# pcb-breakout-bmd300.net
KiCad netlist of a schematic drawn in EAGLE
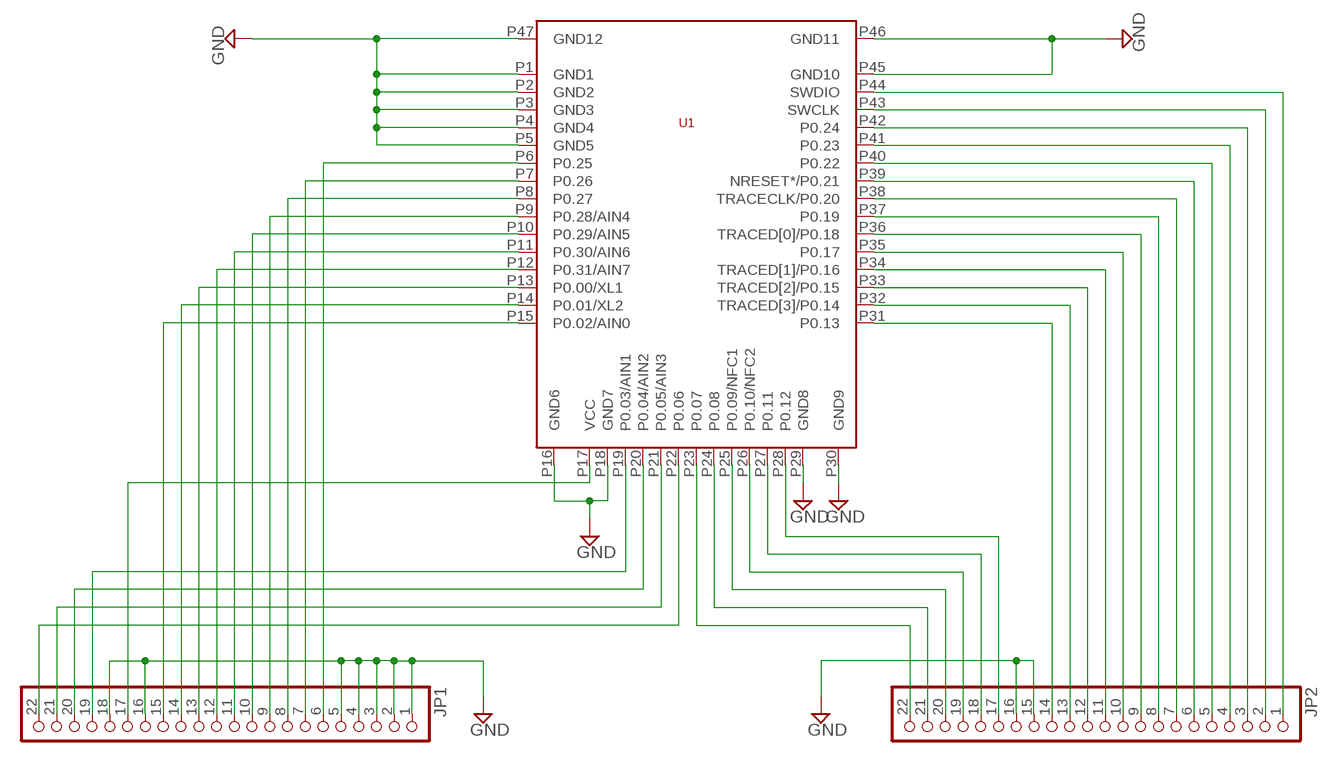
[diagram p0: schematic, sheet 1]

(export (version "E")
  (design (tool "Eeschema 10.0.6"))
  (components
    (comp (ref "JP1")
      (value "PINHD-1X22")
      (footprint "eagle-import:1X22")
      (libsource (lib "eagle-import") (part "PINHD-1X22"))
    )
    (comp (ref "JP2")
      (value "PINHD-1X22")
      (footprint "eagle-import:1X22")
      (libsource (lib "eagle-import") (part "PINHD-1X22"))
    )
    (comp (ref "U1")
      (value "BMD-300")
      (footprint "eagle-import:BMD-300")
      (libsource (lib "eagle-import") (part "BMD-300"))
    )
  )
  (nets
    (net (code "1") (name "GND") (class "Default")
      (node (ref "JP1") (pin "1") (pinfunction "1_1") (pintype "passive"))
      (node (ref "JP1") (pin "16") (pinfunction "16_16") (pintype "passive"))
      (node (ref "JP1") (pin "18") (pinfunction "18_18") (pintype "passive"))
      (node (ref "JP1") (pin "2") (pinfunction "2_2") (pintype "passive"))
      (node (ref "JP1") (pin "3") (pinfunction "3_3") (pintype "passive"))
      (node (ref "JP1") (pin "4") (pinfunction "4_4") (pintype "passive"))
      (node (ref "JP1") (pin "5") (pinfunction "5_5") (pintype "passive"))
      (node (ref "JP2") (pin "15") (pinfunction "15_15") (pintype "passive"))
      (node (ref "JP2") (pin "16") (pinfunction "16_16") (pintype "passive"))
      (node (ref "U1") (pin "P1") (pinfunction "GND1_P1") (pintype "bidirectional"))
      (node (ref "U1") (pin "P16") (pinfunction "GND6_P16") (pintype "bidirectional"))
      (node (ref "U1") (pin "P18") (pinfunction "GND7_P18") (pintype "bidirectional"))
      (node (ref "U1") (pin "P2") (pinfunction "GND2_P2") (pintype "bidirectional"))
      (node (ref "U1") (pin "P29") (pinfunction "GND8_P29") (pintype "bidirectional"))
      (node (ref "U1") (pin "P3") (pinfunction "GND3_P3") (pintype "bidirectional"))
      (node (ref "U1") (pin "P30") (pinfunction "GND9_P30") (pintype "bidirectional"))
      (node (ref "U1") (pin "P4") (pinfunction "GND4_P4") (pintype "bidirectional"))
      (node (ref "U1") (pin "P45") (pinfunction "GND10_P45") (pintype "bidirectional"))
      (node (ref "U1") (pin "P46") (pinfunction "GND11_P46") (pintype "bidirectional"))
      (node (ref "U1") (pin "P47") (pinfunction "GND12_P47") (pintype "bidirectional"))
      (node (ref "U1") (pin "P5") (pinfunction "GND5_P5") (pintype "bidirectional"))
    )
    (net (code "2") (name "Net-(U1-NRESET*{slash}P0.21)") (class "Default")
      (node (ref "JP2") (pin "6") (pinfunction "6_6") (pintype "passive"))
      (node (ref "U1") (pin "P39") (pinfunction "NRESET*/P0.21_P39") (pintype "bidirectional"))
    )
    (net (code "3") (name "Net-(U1-P0.00{slash}XL1)") (class "Default")
      (node (ref "JP1") (pin "13") (pinfunction "13_13") (pintype "passive"))
      (node (ref "U1") (pin "P13") (pinfunction "P0.00/XL1_P13") (pintype "bidirectional"))
    )
    (net (code "4") (name "Net-(U1-P0.01{slash}XL2)") (class "Default")
      (node (ref "JP1") (pin "14") (pinfunction "14_14") (pintype "passive"))
      (node (ref "U1") (pin "P14") (pinfunction "P0.01/XL2_P14") (pintype "bidirectional"))
    )
    (net (code "5") (name "Net-(U1-P0.02{slash}AIN0)") (class "Default")
      (node (ref "JP1") (pin "15") (pinfunction "15_15") (pintype "passive"))
      (node (ref "U1") (pin "P15") (pinfunction "P0.02/AIN0_P15") (pintype "bidirectional"))
    )
    (net (code "6") (name "Net-(U1-P0.03{slash}AIN1)") (class "Default")
      (node (ref "JP1") (pin "19") (pinfunction "19_19") (pintype "passive"))
      (node (ref "U1") (pin "P19") (pinfunction "P0.03/AIN1_P19") (pintype "bidirectional"))
    )
    (net (code "7") (name "Net-(U1-P0.04{slash}AIN2)") (class "Default")
      (node (ref "JP1") (pin "20") (pinfunction "20_20") (pintype "passive"))
      (node (ref "U1") (pin "P20") (pinfunction "P0.04/AIN2_P20") (pintype "bidirectional"))
    )
    (net (code "8") (name "Net-(U1-P0.05{slash}AIN3)") (class "Default")
      (node (ref "JP1") (pin "21") (pinfunction "21_21") (pintype "passive"))
      (node (ref "U1") (pin "P21") (pinfunction "P0.05/AIN3_P21") (pintype "bidirectional"))
    )
    (net (code "9") (name "Net-(U1-P0.06)") (class "Default")
      (node (ref "JP1") (pin "22") (pinfunction "22_22") (pintype "passive"))
      (node (ref "U1") (pin "P22") (pinfunction "P0.06_P22") (pintype "bidirectional"))
    )
    (net (code "10") (name "Net-(U1-P0.07)") (class "Default")
      (node (ref "JP2") (pin "22") (pinfunction "22_22") (pintype "passive"))
      (node (ref "U1") (pin "P23") (pinfunction "P0.07_P23") (pintype "bidirectional"))
    )
    (net (code "11") (name "Net-(U1-P0.08)") (class "Default")
      (node (ref "JP2") (pin "21") (pinfunction "21_21") (pintype "passive"))
      (node (ref "U1") (pin "P24") (pinfunction "P0.08_P24") (pintype "bidirectional"))
    )
    (net (code "12") (name "Net-(U1-P0.09{slash}NFC1)") (class "Default")
      (node (ref "JP2") (pin "20") (pinfunction "20_20") (pintype "passive"))
      (node (ref "U1") (pin "P25") (pinfunction "P0.09/NFC1_P25") (pintype "bidirectional"))
    )
    (net (code "13") (name "Net-(U1-P0.10{slash}NFC2)") (class "Default")
      (node (ref "JP2") (pin "19") (pinfunction "19_19") (pintype "passive"))
      (node (ref "U1") (pin "P26") (pinfunction "P0.10/NFC2_P26") (pintype "bidirectional"))
    )
    (net (code "14") (name "Net-(U1-P0.11)") (class "Default")
      (node (ref "JP2") (pin "18") (pinfunction "18_18") (pintype "passive"))
      (node (ref "U1") (pin "P27") (pinfunction "P0.11_P27") (pintype "bidirectional"))
    )
    (net (code "15") (name "Net-(U1-P0.12)") (class "Default")
      (node (ref "JP2") (pin "17") (pinfunction "17_17") (pintype "passive"))
      (node (ref "U1") (pin "P28") (pinfunction "P0.12_P28") (pintype "bidirectional"))
    )
    (net (code "16") (name "Net-(U1-P0.13)") (class "Default")
      (node (ref "JP2") (pin "14") (pinfunction "14_14") (pintype "passive"))
      (node (ref "U1") (pin "P31") (pinfunction "P0.13_P31") (pintype "bidirectional"))
    )
    (net (code "17") (name "Net-(U1-P0.17)") (class "Default")
      (node (ref "JP2") (pin "10") (pinfunction "10_10") (pintype "passive"))
      (node (ref "U1") (pin "P35") (pinfunction "P0.17_P35") (pintype "bidirectional"))
    )
    (net (code "18") (name "Net-(U1-P0.19)") (class "Default")
      (node (ref "JP2") (pin "8") (pinfunction "8_8") (pintype "passive"))
      (node (ref "U1") (pin "P37") (pinfunction "P0.19_P37") (pintype "bidirectional"))
    )
    (net (code "19") (name "Net-(U1-P0.22)") (class "Default")
      (node (ref "JP2") (pin "5") (pinfunction "5_5") (pintype "passive"))
      (node (ref "U1") (pin "P40") (pinfunction "P0.22_P40") (pintype "bidirectional"))
    )
    (net (code "20") (name "Net-(U1-P0.23)") (class "Default")
      (node (ref "JP2") (pin "4") (pinfunction "4_4") (pintype "passive"))
      (node (ref "U1") (pin "P41") (pinfunction "P0.23_P41") (pintype "bidirectional"))
    )
    (net (code "21") (name "Net-(U1-P0.24)") (class "Default")
      (node (ref "JP2") (pin "3") (pinfunction "3_3") (pintype "passive"))
      (node (ref "U1") (pin "P42") (pinfunction "P0.24_P42") (pintype "bidirectional"))
    )
    (net (code "22") (name "Net-(U1-P0.25)") (class "Default")
      (node (ref "JP1") (pin "6") (pinfunction "6_6") (pintype "passive"))
      (node (ref "U1") (pin "P6") (pinfunction "P0.25_P6") (pintype "bidirectional"))
    )
    (net (code "23") (name "Net-(U1-P0.26)") (class "Default")
      (node (ref "JP1") (pin "7") (pinfunction "7_7") (pintype "passive"))
      (node (ref "U1") (pin "P7") (pinfunction "P0.26_P7") (pintype "bidirectional"))
    )
    (net (code "24") (name "Net-(U1-P0.27)") (class "Default")
      (node (ref "JP1") (pin "8") (pinfunction "8_8") (pintype "passive"))
      (node (ref "U1") (pin "P8") (pinfunction "P0.27_P8") (pintype "bidirectional"))
    )
    (net (code "25") (name "Net-(U1-P0.28{slash}AIN4)") (class "Default")
      (node (ref "JP1") (pin "9") (pinfunction "9_9") (pintype "passive"))
      (node (ref "U1") (pin "P9") (pinfunction "P0.28/AIN4_P9") (pintype "bidirectional"))
    )
    (net (code "26") (name "Net-(U1-P0.29{slash}AIN5)") (class "Default")
      (node (ref "JP1") (pin "10") (pinfunction "10_10") (pintype "passive"))
      (node (ref "U1") (pin "P10") (pinfunction "P0.29/AIN5_P10") (pintype "bidirectional"))
    )
    (net (code "27") (name "Net-(U1-P0.30{slash}AIN6)") (class "Default")
      (node (ref "JP1") (pin "11") (pinfunction "11_11") (pintype "passive"))
      (node (ref "U1") (pin "P11") (pinfunction "P0.30/AIN6_P11") (pintype "bidirectional"))
    )
    (net (code "28") (name "Net-(U1-P0.31{slash}AIN7)") (class "Default")
      (node (ref "JP1") (pin "12") (pinfunction "12_12") (pintype "passive"))
      (node (ref "U1") (pin "P12") (pinfunction "P0.31/AIN7_P12") (pintype "bidirectional"))
    )
    (net (code "29") (name "Net-(U1-SWCLK)") (class "Default")
      (node (ref "JP2") (pin "2") (pinfunction "2_2") (pintype "passive"))
      (node (ref "U1") (pin "P43") (pinfunction "SWCLK_P43") (pintype "bidirectional"))
    )
    (net (code "30") (name "Net-(U1-SWDIO)") (class "Default")
      (node (ref "JP2") (pin "1") (pinfunction "1_1") (pintype "passive"))
      (node (ref "U1") (pin "P44") (pinfunction "SWDIO_P44") (pintype "bidirectional"))
    )
    (net (code "31") (name "Net-(U1-TRACECLK{slash}P0.20)") (class "Default")
      (node (ref "JP2") (pin "7") (pinfunction "7_7") (pintype "passive"))
      (node (ref "U1") (pin "P38") (pinfunction "TRACECLK/P0.20_P38") (pintype "bidirectional"))
    )
    (net (code "32") (name "Net-(U1-TRACED[0]{slash}P0.18)") (class "Default")
      (node (ref "JP2") (pin "9") (pinfunction "9_9") (pintype "passive"))
      (node (ref "U1") (pin "P36") (pinfunction "TRACED[0]/P0.18_P36") (pintype "bidirectional"))
    )
    (net (code "33") (name "Net-(U1-TRACED[1]{slash}P0.16)") (class "Default")
      (node (ref "JP2") (pin "11") (pinfunction "11_11") (pintype "passive"))
      (node (ref "U1") (pin "P34") (pinfunction "TRACED[1]/P0.16_P34") (pintype "bidirectional"))
    )
    (net (code "34") (name "Net-(U1-TRACED[2]{slash}P0.15)") (class "Default")
      (node (ref "JP2") (pin "12") (pinfunction "12_12") (pintype "passive"))
      (node (ref "U1") (pin "P33") (pinfunction "TRACED[2]/P0.15_P33") (pintype "bidirectional"))
    )
    (net (code "35") (name "Net-(U1-TRACED[3]{slash}P0.14)") (class "Default")
      (node (ref "JP2") (pin "13") (pinfunction "13_13") (pintype "passive"))
      (node (ref "U1") (pin "P32") (pinfunction "TRACED[3]/P0.14_P32") (pintype "bidirectional"))
    )
    (net (code "36") (name "Net-(U1-VCC)") (class "Default")
      (node (ref "JP1") (pin "17") (pinfunction "17_17") (pintype "passive"))
      (node (ref "U1") (pin "P17") (pinfunction "VCC_P17") (pintype "bidirectional"))
    )
  )
)
